# PLmodule.net
KiCad netlist of a schematic drawn in Altium Designer
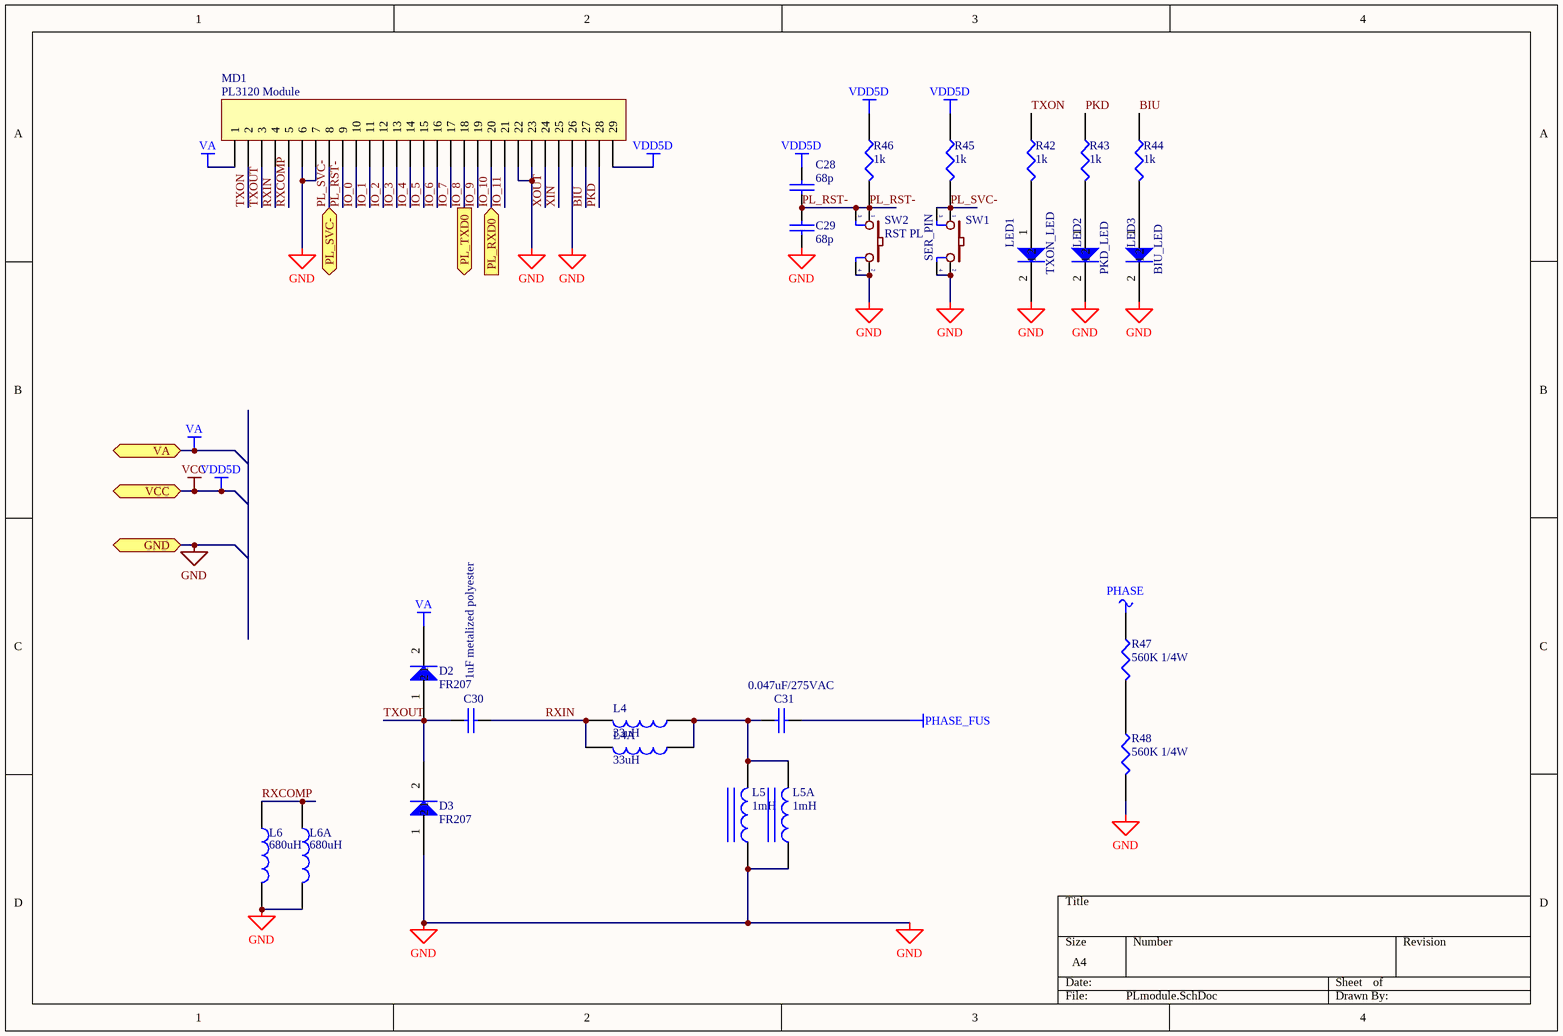
[diagram p0: PLmodule.SchDoc]

(export (version "E")
  (design (tool "Eeschema 10.0.6"))
  (components
    (comp (ref "C28")
      (value "68p")
      (footprint "C6-0805_N")
      (description "Capacitor")
      (libsource (lib "*") (part "CAP"))
    )
    (comp (ref "C29")
      (value "68p")
      (footprint "C6-0805_N")
      (description "Capacitor")
      (libsource (lib "*") (part "CAP"))
    )
    (comp (ref "C30")
      (value "1uF metalized polyester")
      (footprint "CSIP3")
      (description "Capacitor")
      (libsource (lib "*") (part "CAP"))
    )
    (comp (ref "C31")
      (value "0.047uF/275VAC")
      (footprint "100n400v")
      (description "X2 0.047uF/275VAC")
      (libsource (lib "*") (part "CAP"))
    )
    (comp (ref "D2") (value "FR207") (footprint "DO-214AB") (libsource (lib "*") (part "DIODE")))
    (comp (ref "D3") (value "FR207") (footprint "DO-214AB") (libsource (lib "*") (part "DIODE")))
    (comp (ref "L4")
      (value "33uH")
      (footprint "6D28")
      (description "0805 inductor")
      (libsource (lib "*") (part "INDUCTOR"))
    )
    (comp (ref "L4A")
      (value "33uH")
      (footprint "Axial-0.3")
      (description "Axial inductor")
      (libsource (lib "*") (part "INDUCTOR"))
    )
    (comp (ref "L5") (value "1mH") (footprint "6-0805_N") (libsource (lib "*") (part "INDUCTOR IRON")))
    (comp (ref "L5A") (value "1mH") (footprint "AXIAL-0.3") (libsource (lib "*") (part "INDUCTOR IRON")))
    (comp (ref "L6") (value "680uH") (footprint "6-0805_N") (libsource (lib "") (part "INDUCTOR_1")))
    (comp (ref "L6A") (value "680uH") (footprint "AXIAL-0.3") (libsource (lib "") (part "INDUCTOR_1")))
    (comp (ref "LED1") (value "TXON_LED") (footprint "led3mm") (libsource (lib "*") (part "DIODE")))
    (comp (ref "LED2") (value "PKD_LED") (footprint "led3mm") (libsource (lib "*") (part "DIODE")))
    (comp (ref "LED3") (value "BIU_LED") (footprint "led3mm") (libsource (lib "*") (part "DIODE")))
    (comp (ref "MD1")
      (value "PL3120 Module")
      (footprint "ECHELONMODULE")
      (description "Connector")
      (libsource (lib "*") (part "CON29"))
    )
    (comp (ref "R42") (value "1k") (footprint "6-0805_N") (libsource (lib "*") (part "RES1")))
    (comp (ref "R43") (value "1k") (footprint "6-0805_N") (libsource (lib "*") (part "RES1")))
    (comp (ref "R44") (value "1k") (footprint "6-0805_N") (libsource (lib "*") (part "RES1")))
    (comp (ref "R45") (value "1k") (footprint "6-0805_N") (libsource (lib "*") (part "RES1")))
    (comp (ref "R46") (value "1k") (footprint "6-0805_N") (libsource (lib "*") (part "RES1")))
    (comp (ref "R47") (value "560K 1/4W") (footprint "R3216[1206]") (libsource (lib "*") (part "RES1")))
    (comp (ref "R48") (value "560K 1/4W") (footprint "R3216[1206]") (libsource (lib "*") (part "RES1")))
    (comp (ref "SW1")
      (value "SER_PIN")
      (footprint "SW-4P-S")
      (description "Switch button 4 pin")
      (libsource (lib "syhaunguyen") (part "SW4-1"))
    )
    (comp (ref "SW2")
      (value "RST PL")
      (footprint "SW-4P-S")
      (description "Switch button 4 pin")
      (libsource (lib "syhaunguyen") (part "SW4-1"))
    )
  )
  (nets
    (net (code "1") (name "/BIU") (class "Default")
      (node (ref "MD1") (pin "27") (pinfunction "27_27") (pintype "passive"))
      (node (ref "R44") (pin "1") (pinfunction "1_1") (pintype "passive"))
    )
    (net (code "2") (name "/IO_0") (class "Default")
      (node (ref "MD1") (pin "10") (pinfunction "10_10") (pintype "passive"))
    )
    (net (code "3") (name "/IO_1") (class "Default")
      (node (ref "MD1") (pin "11") (pinfunction "11_11") (pintype "passive"))
    )
    (net (code "4") (name "/IO_2") (class "Default")
      (node (ref "MD1") (pin "12") (pinfunction "12_12") (pintype "passive"))
    )
    (net (code "5") (name "/IO_3") (class "Default")
      (node (ref "MD1") (pin "13") (pinfunction "13_13") (pintype "passive"))
    )
    (net (code "6") (name "/IO_4") (class "Default")
      (node (ref "MD1") (pin "14") (pinfunction "14_14") (pintype "passive"))
    )
    (net (code "7") (name "/IO_5") (class "Default")
      (node (ref "MD1") (pin "15") (pinfunction "15_15") (pintype "passive"))
    )
    (net (code "8") (name "/IO_6") (class "Default")
      (node (ref "MD1") (pin "16") (pinfunction "16_16") (pintype "passive"))
    )
    (net (code "9") (name "/IO_7") (class "Default")
      (node (ref "MD1") (pin "17") (pinfunction "17_17") (pintype "passive"))
    )
    (net (code "10") (name "/IO_8") (class "Default")
      (node (ref "MD1") (pin "18") (pinfunction "18_18") (pintype "passive"))
    )
    (net (code "11") (name "/IO_9") (class "Default")
      (node (ref "MD1") (pin "19") (pinfunction "19_19") (pintype "passive"))
    )
    (net (code "12") (name "/IO_10") (class "Default")
      (node (ref "MD1") (pin "20") (pinfunction "20_20") (pintype "passive"))
    )
    (net (code "13") (name "/IO_11") (class "Default")
      (node (ref "MD1") (pin "21") (pinfunction "21_21") (pintype "passive"))
    )
    (net (code "14") (name "/PKD") (class "Default")
      (node (ref "MD1") (pin "28") (pinfunction "28_28") (pintype "passive"))
      (node (ref "R43") (pin "1") (pinfunction "1_1") (pintype "passive"))
    )
    (net (code "15") (name "/PL_RST-") (class "Default")
      (node (ref "C28") (pin "1") (pinfunction "1_1") (pintype "passive"))
      (node (ref "C29") (pin "1") (pinfunction "1_1") (pintype "passive"))
      (node (ref "MD1") (pin "9") (pinfunction "9_9") (pintype "passive"))
      (node (ref "R46") (pin "2") (pinfunction "2_2") (pintype "passive"))
      (node (ref "SW2") (pin "1") (pinfunction "1_1") (pintype "passive"))
      (node (ref "SW2") (pin "3") (pinfunction "3_3") (pintype "passive"))
    )
    (net (code "16") (name "/PL_SVC-") (class "Default")
      (node (ref "MD1") (pin "8") (pinfunction "8_8") (pintype "passive"))
      (node (ref "R45") (pin "2") (pinfunction "2_2") (pintype "passive"))
      (node (ref "SW1") (pin "1") (pinfunction "1_1") (pintype "passive"))
      (node (ref "SW1") (pin "3") (pinfunction "3_3") (pintype "passive"))
    )
    (net (code "17") (name "/RXCOMP") (class "Default")
      (node (ref "L6") (pin "1") (pinfunction "1_1") (pintype "passive"))
      (node (ref "L6A") (pin "1") (pinfunction "1_1") (pintype "passive"))
      (node (ref "MD1") (pin "5") (pinfunction "5_5") (pintype "passive"))
    )
    (net (code "18") (name "/RXIN") (class "Default")
      (node (ref "C30") (pin "2") (pinfunction "2_2") (pintype "passive"))
      (node (ref "L4") (pin "1") (pinfunction "1_1") (pintype "passive"))
      (node (ref "L4A") (pin "1") (pinfunction "1_1") (pintype "passive"))
      (node (ref "MD1") (pin "4") (pinfunction "4_4") (pintype "passive"))
    )
    (net (code "19") (name "/TXON") (class "Default")
      (node (ref "MD1") (pin "2") (pinfunction "2_2") (pintype "passive"))
      (node (ref "R42") (pin "1") (pinfunction "1_1") (pintype "passive"))
    )
    (net (code "20") (name "/TXOUT") (class "Default")
      (node (ref "C30") (pin "1") (pinfunction "1_1") (pintype "passive"))
      (node (ref "D2") (pin "1") (pinfunction "1_1") (pintype "passive"))
      (node (ref "D3") (pin "2") (pinfunction "2_2") (pintype "passive"))
      (node (ref "MD1") (pin "3") (pinfunction "3_3") (pintype "passive"))
    )
    (net (code "21") (name "/XIN") (class "Default")
      (node (ref "MD1") (pin "25") (pinfunction "25_25") (pintype "passive"))
    )
    (net (code "22") (name "/XOUT") (class "Default")
      (node (ref "MD1") (pin "24") (pinfunction "24_24") (pintype "passive"))
    )
    (net (code "23") (name "GND") (class "Default")
      (node (ref "C29") (pin "2") (pinfunction "2_2") (pintype "passive"))
      (node (ref "D3") (pin "1") (pinfunction "1_1") (pintype "passive"))
      (node (ref "L5") (pin "2") (pinfunction "2_2") (pintype "passive"))
      (node (ref "L5A") (pin "2") (pinfunction "2_2") (pintype "passive"))
      (node (ref "L6") (pin "2") (pinfunction "2_2") (pintype "passive"))
      (node (ref "L6A") (pin "2") (pinfunction "2_2") (pintype "passive"))
      (node (ref "LED1") (pin "2") (pinfunction "2_2") (pintype "passive"))
      (node (ref "LED2") (pin "2") (pinfunction "2_2") (pintype "passive"))
      (node (ref "LED3") (pin "2") (pinfunction "2_2") (pintype "passive"))
      (node (ref "MD1") (pin "22") (pinfunction "22_22") (pintype "passive"))
      (node (ref "MD1") (pin "23") (pinfunction "23_23") (pintype "passive"))
      (node (ref "MD1") (pin "26") (pinfunction "26_26") (pintype "passive"))
      (node (ref "MD1") (pin "6") (pinfunction "6_6") (pintype "passive"))
      (node (ref "MD1") (pin "7") (pinfunction "7_7") (pintype "passive"))
      (node (ref "R48") (pin "1") (pinfunction "1_1") (pintype "passive"))
      (node (ref "SW1") (pin "2") (pinfunction "2_2") (pintype "passive"))
      (node (ref "SW1") (pin "4") (pinfunction "4_4") (pintype "passive"))
      (node (ref "SW2") (pin "2") (pinfunction "2_2") (pintype "passive"))
      (node (ref "SW2") (pin "4") (pinfunction "4_4") (pintype "passive"))
    )
    (net (code "24") (name "Net-(C31-Pad2)") (class "Default")
      (node (ref "C31") (pin "2") (pinfunction "2_2") (pintype "passive"))
      (node (ref "L4") (pin "2") (pinfunction "2_2") (pintype "passive"))
      (node (ref "L4A") (pin "2") (pinfunction "2_2") (pintype "passive"))
      (node (ref "L5") (pin "1") (pinfunction "1_1") (pintype "passive"))
      (node (ref "L5A") (pin "1") (pinfunction "1_1") (pintype "passive"))
    )
    (net (code "25") (name "Net-(LED1-Pad1)") (class "Default")
      (node (ref "LED1") (pin "1") (pinfunction "1_1") (pintype "passive"))
      (node (ref "R42") (pin "2") (pinfunction "2_2") (pintype "passive"))
    )
    (net (code "26") (name "Net-(LED2-Pad1)") (class "Default")
      (node (ref "LED2") (pin "1") (pinfunction "1_1") (pintype "passive"))
      (node (ref "R43") (pin "2") (pinfunction "2_2") (pintype "passive"))
    )
    (net (code "27") (name "Net-(LED3-Pad1)") (class "Default")
      (node (ref "LED3") (pin "1") (pinfunction "1_1") (pintype "passive"))
      (node (ref "R44") (pin "2") (pinfunction "2_2") (pintype "passive"))
    )
    (net (code "28") (name "Net-(R47-Pad1)") (class "Default")
      (node (ref "R47") (pin "1") (pinfunction "1_1") (pintype "passive"))
      (node (ref "R48") (pin "2") (pinfunction "2_2") (pintype "passive"))
    )
    (net (code "29") (name "PHASE") (class "Default")
      (node (ref "R47") (pin "2") (pinfunction "2_2") (pintype "passive"))
    )
    (net (code "30") (name "PHASE_FUS") (class "Default")
      (node (ref "C31") (pin "1") (pinfunction "1_1") (pintype "passive"))
    )
    (net (code "31") (name "VA") (class "Default")
      (node (ref "D2") (pin "2") (pinfunction "2_2") (pintype "passive"))
      (node (ref "MD1") (pin "1") (pinfunction "1_1") (pintype "passive"))
    )
    (net (code "32") (name "VCC") (class "Default")
      (node (ref "C28") (pin "2") (pinfunction "2_2") (pintype "passive"))
      (node (ref "MD1") (pin "29") (pinfunction "29_29") (pintype "passive"))
      (node (ref "R45") (pin "1") (pinfunction "1_1") (pintype "passive"))
      (node (ref "R46") (pin "1") (pinfunction "1_1") (pintype "passive"))
    )
  )
)
